# ic-mhm-encoder-buffer-output-only.net
KiCad netlist of a schematic drawn in EAGLE
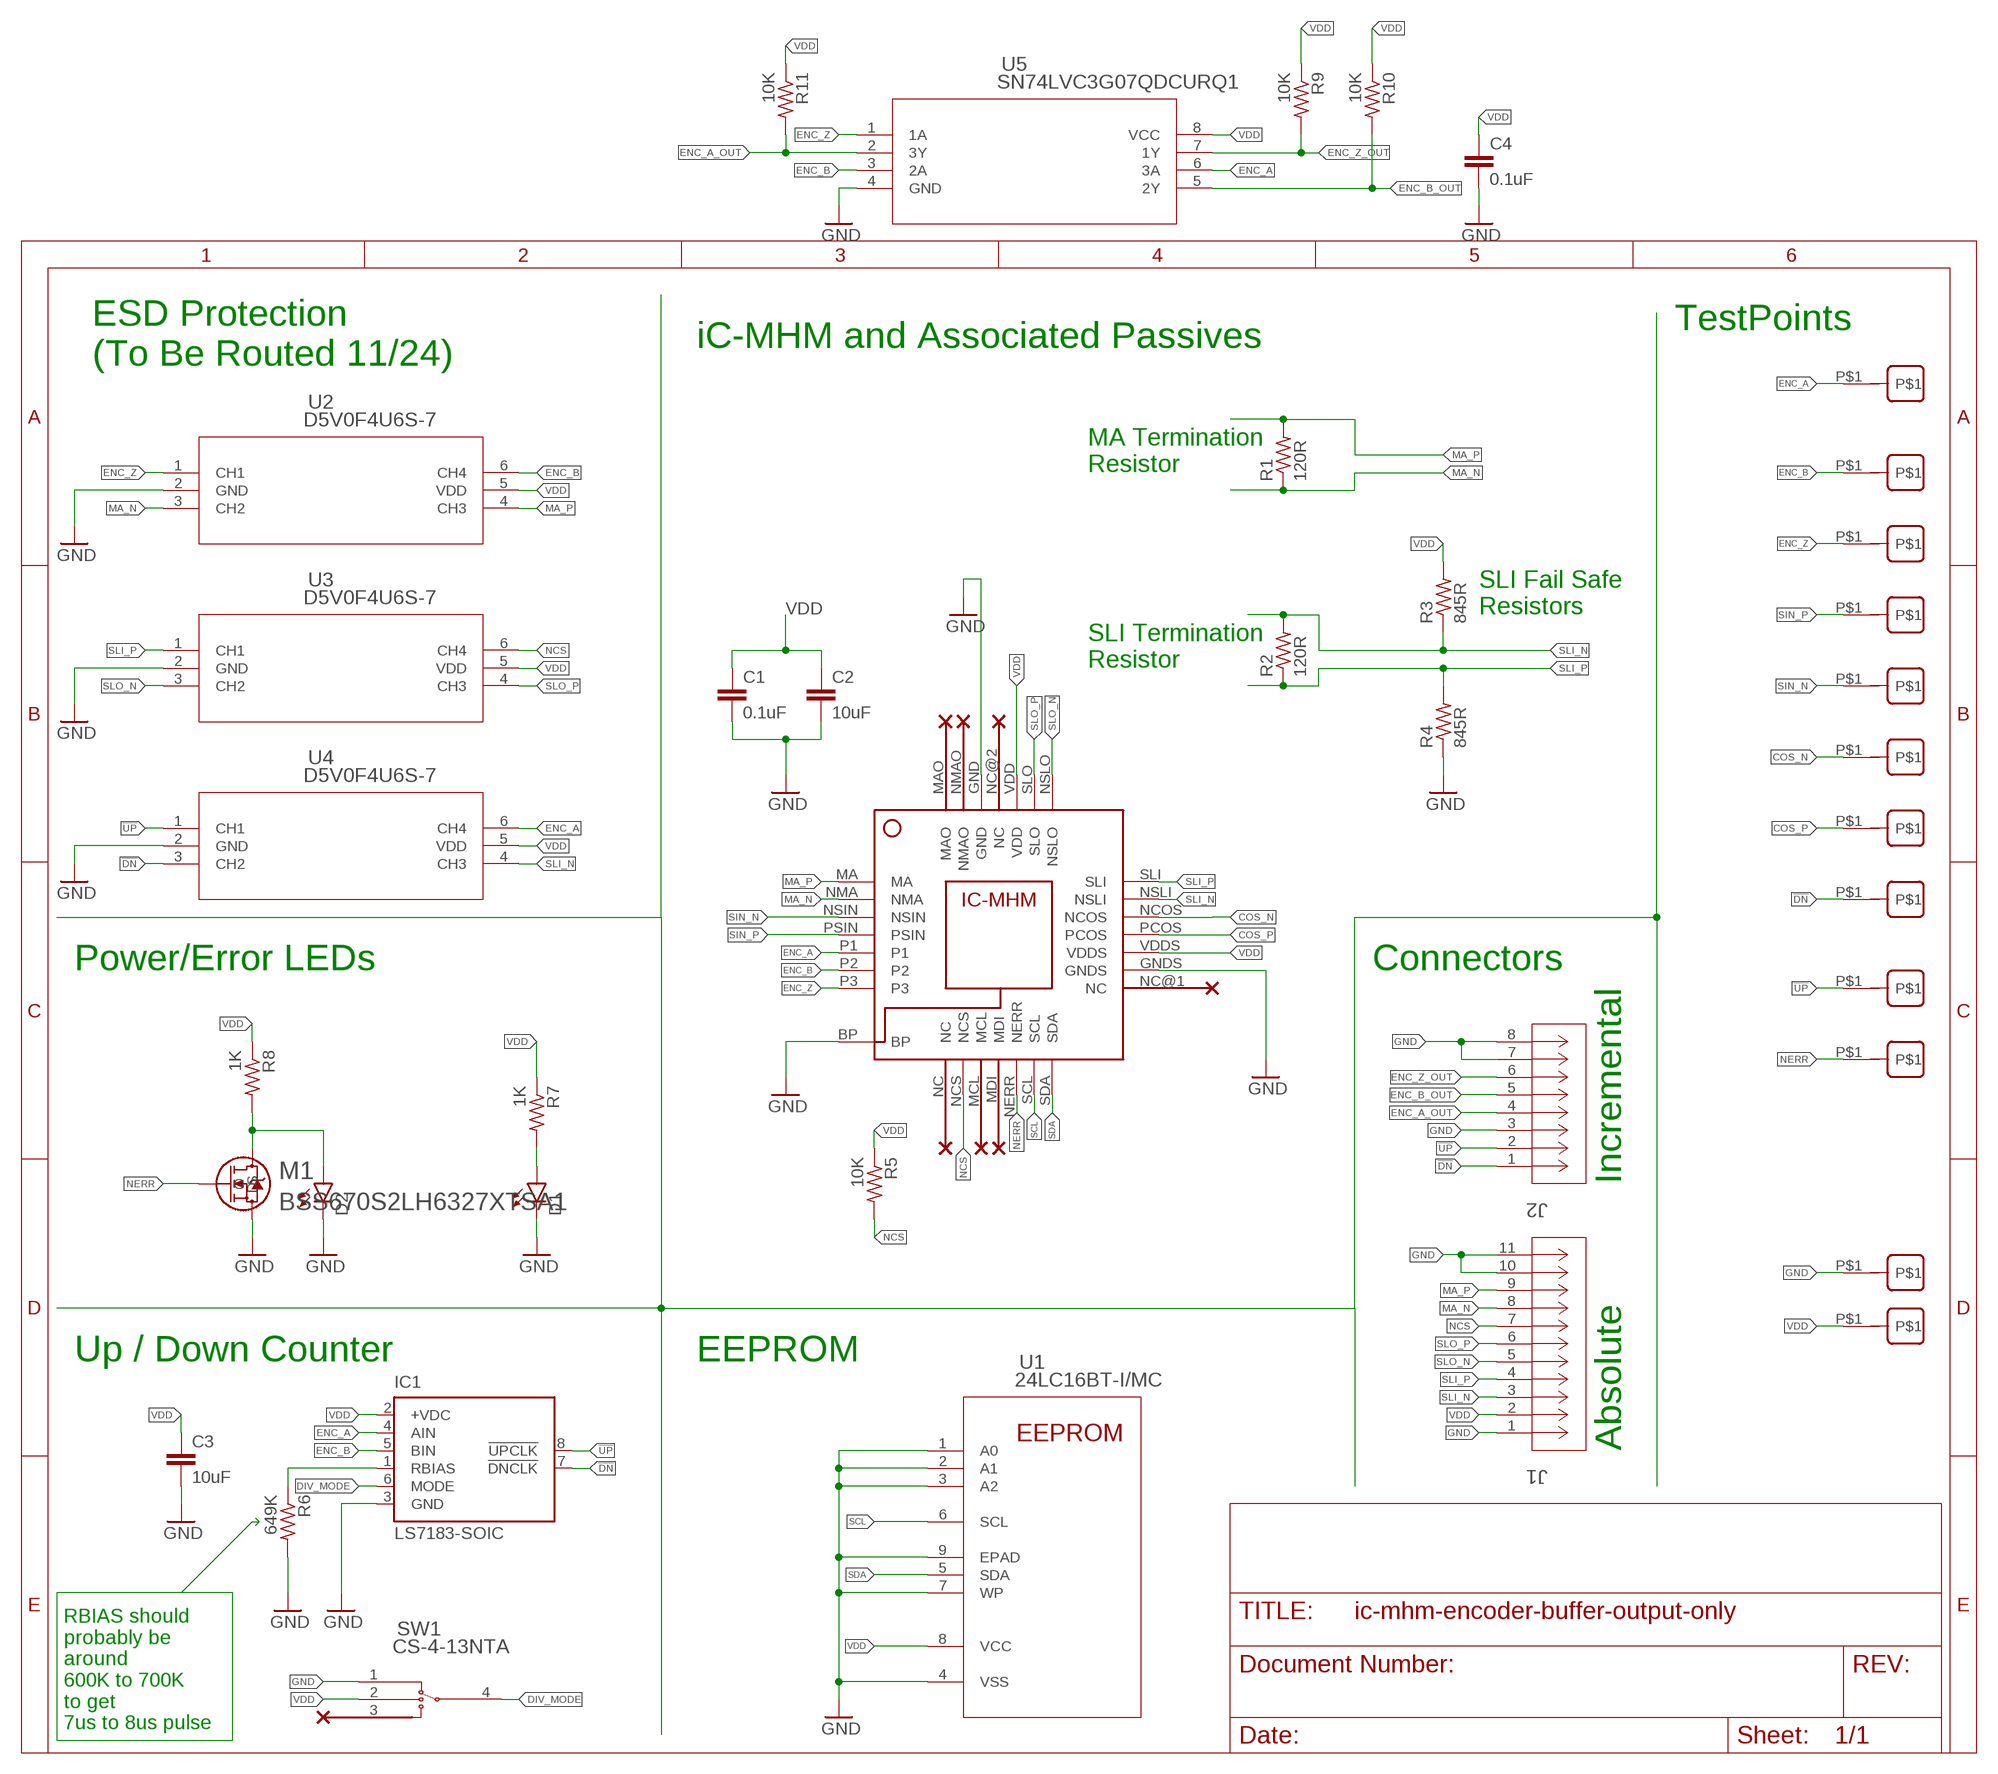
[diagram p0: schematic, sheet 1]

(export (version "E")
  (design (tool "Eeschema 10.0.6"))
  (components
    (comp (ref "C1")
      (value "0.1uF")
      (footprint "eagle-import:C0603")
      (libsource (lib "eagle-import") (part "C-EUC0603"))
    )
    (comp (ref "C2")
      (value "10uF")
      (footprint "eagle-import:C0805")
      (libsource (lib "eagle-import") (part "C-EUC0805"))
    )
    (comp (ref "C3")
      (value "10uF")
      (footprint "eagle-import:C0805")
      (libsource (lib "eagle-import") (part "C-EUC0805"))
    )
    (comp (ref "C4")
      (value "0.1uF")
      (footprint "eagle-import:C0603")
      (libsource (lib "eagle-import") (part "C-EUC0603"))
    )
    (comp (ref "D1")
      (value "LEDSML0603")
      (footprint "eagle-import:SML0603")
      (libsource (lib "eagle-import") (part "LEDSML0603"))
    )
    (comp (ref "D2")
      (value "LEDSML0603")
      (footprint "eagle-import:SML0603")
      (libsource (lib "eagle-import") (part "LEDSML0603"))
    )
    (comp (ref "IC1")
      (value "LS7183-SOIC")
      (footprint "eagle-import:SOIC08")
      (fields
        (field (name "DIGI-KEY_PART_NUMBER") "2808-LS7183N-S-ND")
        (field (name "MF") "LSI")
        (field (name "MP") "LS7183")
      )
      (libsource (lib "eagle-import") (part "LS7183-SOIC"))
    )
    (comp (ref "J1")
      (value "2023960907")
      (footprint "eagle-import:CON_2023960907")
      (fields (field (name "COPYRIGHT") "Copyright (C) 2021 Ultra Librarian. All rights reserved."))
      (libsource (lib "eagle-import") (part "2023960907"))
    )
    (comp (ref "J2")
      (value "2023960607")
      (footprint "eagle-import:CON_2023960607")
      (fields (field (name "COPYRIGHT") "Copyright (C) 2021 Ultra Librarian. All rights reserved."))
      (libsource (lib "eagle-import") (part "2023960607"))
    )
    (comp (ref "M1")
      (value "BSS670S2LH6327XTSA1")
      (footprint "eagle-import:PG-SOT23-3-5_INF")
      (fields (field (name "COPYRIGHT") "Copyright (C) 2021 Ultra Librarian. All rights reserved."))
      (libsource (lib "eagle-import") (part "BSS670S2LH6327XTSA1"))
    )
    (comp (ref "R1")
      (value "120R")
      (footprint "eagle-import:R0603")
      (libsource (lib "eagle-import") (part "R-US_R0603"))
    )
    (comp (ref "R2")
      (value "120R")
      (footprint "eagle-import:R0603")
      (libsource (lib "eagle-import") (part "R-US_R0603"))
    )
    (comp (ref "R3")
      (value "845R")
      (footprint "eagle-import:R0603")
      (libsource (lib "eagle-import") (part "R-US_R0603"))
    )
    (comp (ref "R4")
      (value "845R")
      (footprint "eagle-import:R0603")
      (libsource (lib "eagle-import") (part "R-US_R0603"))
    )
    (comp (ref "R5")
      (value "10K")
      (footprint "eagle-import:R0603")
      (libsource (lib "eagle-import") (part "R-US_R0603"))
    )
    (comp (ref "R6")
      (value "649K")
      (footprint "eagle-import:R0603")
      (libsource (lib "eagle-import") (part "R-US_R0603"))
    )
    (comp (ref "R7")
      (value "1K")
      (footprint "eagle-import:R0603")
      (libsource (lib "eagle-import") (part "R-US_R0603"))
    )
    (comp (ref "R8")
      (value "1K")
      (footprint "eagle-import:R0603")
      (libsource (lib "eagle-import") (part "R-US_R0603"))
    )
    (comp (ref "R9")
      (value "10K")
      (footprint "eagle-import:R0603")
      (libsource (lib "eagle-import") (part "R-US_R0603"))
    )
    (comp (ref "R10")
      (value "10K")
      (footprint "eagle-import:R0603")
      (libsource (lib "eagle-import") (part "R-US_R0603"))
    )
    (comp (ref "R11")
      (value "10K")
      (footprint "eagle-import:R0603")
      (libsource (lib "eagle-import") (part "R-US_R0603"))
    )
    (comp (ref "SW1")
      (value "CS-4-13NTA")
      (footprint "eagle-import:CS-4-13NA_NDC")
      (fields (field (name "COPYRIGHT") "Copyright (C) 2021 Ultra Librarian. All rights reserved."))
      (libsource (lib "eagle-import") (part "CS-4-13NTA"))
    )
    (comp (ref "U$1")
      (value "IC-MHM")
      (footprint "eagle-import:IC-MHM")
      (libsource (lib "eagle-import") (part "IC-MHM"))
    )
    (comp (ref "U$2")
      (value "TESTPOINT_S1751-46")
      (footprint "eagle-import:TESTPOINT_S1751-46")
      (libsource (lib "eagle-import") (part "TESTPOINT_S1751-46"))
    )
    (comp (ref "U$3")
      (value "TESTPOINT_S1751-46")
      (footprint "eagle-import:TESTPOINT_S1751-46")
      (libsource (lib "eagle-import") (part "TESTPOINT_S1751-46"))
    )
    (comp (ref "U$4")
      (value "TESTPOINT_S1751-46")
      (footprint "eagle-import:TESTPOINT_S1751-46")
      (libsource (lib "eagle-import") (part "TESTPOINT_S1751-46"))
    )
    (comp (ref "U$5")
      (value "TESTPOINT_S1751-46")
      (footprint "eagle-import:TESTPOINT_S1751-46")
      (libsource (lib "eagle-import") (part "TESTPOINT_S1751-46"))
    )
    (comp (ref "U$6")
      (value "TESTPOINT_S1751-46")
      (footprint "eagle-import:TESTPOINT_S1751-46")
      (libsource (lib "eagle-import") (part "TESTPOINT_S1751-46"))
    )
    (comp (ref "U$7")
      (value "TESTPOINT_S1751-46")
      (footprint "eagle-import:TESTPOINT_S1751-46")
      (libsource (lib "eagle-import") (part "TESTPOINT_S1751-46"))
    )
    (comp (ref "U$8")
      (value "TESTPOINT_S1751-46")
      (footprint "eagle-import:TESTPOINT_S1751-46")
      (libsource (lib "eagle-import") (part "TESTPOINT_S1751-46"))
    )
    (comp (ref "U$9")
      (value "TESTPOINT_S1751-46")
      (footprint "eagle-import:TESTPOINT_S1751-46")
      (libsource (lib "eagle-import") (part "TESTPOINT_S1751-46"))
    )
    (comp (ref "U$10")
      (value "TESTPOINT_S1751-46")
      (footprint "eagle-import:TESTPOINT_S1751-46")
      (libsource (lib "eagle-import") (part "TESTPOINT_S1751-46"))
    )
    (comp (ref "U$11")
      (value "TESTPOINT_S1751-46")
      (footprint "eagle-import:TESTPOINT_S1751-46")
      (libsource (lib "eagle-import") (part "TESTPOINT_S1751-46"))
    )
    (comp (ref "U$15")
      (value "TESTPOINT_S1751-46")
      (footprint "eagle-import:TESTPOINT_S1751-46")
      (libsource (lib "eagle-import") (part "TESTPOINT_S1751-46"))
    )
    (comp (ref "U$16")
      (value "TESTPOINT_S1751-46")
      (footprint "eagle-import:TESTPOINT_S1751-46")
      (libsource (lib "eagle-import") (part "TESTPOINT_S1751-46"))
    )
    (comp (ref "U1")
      (value "24LC16BT-I/MC")
      (footprint "eagle-import:DFN8_2X3MC_MCH")
      (fields (field (name "COPYRIGHT") "Copyright (C) 2021 Ultra Librarian. All rights reserved."))
      (libsource (lib "eagle-import") (part "24LC16BT-I/MC"))
    )
    (comp (ref "U2")
      (value "D5V0F4U6S-7")
      (footprint "eagle-import:SOT-363_DIO")
      (fields (field (name "COPYRIGHT") "Copyright (C) 2021 Ultra Librarian. All rights reserved."))
      (libsource (lib "eagle-import") (part "D5V0F4U6S-7"))
    )
    (comp (ref "U3")
      (value "D5V0F4U6S-7")
      (footprint "eagle-import:SOT-363_DIO")
      (fields (field (name "COPYRIGHT") "Copyright (C) 2021 Ultra Librarian. All rights reserved."))
      (libsource (lib "eagle-import") (part "D5V0F4U6S-7"))
    )
    (comp (ref "U4")
      (value "D5V0F4U6S-7")
      (footprint "eagle-import:SOT-363_DIO")
      (fields (field (name "COPYRIGHT") "Copyright (C) 2021 Ultra Librarian. All rights reserved."))
      (libsource (lib "eagle-import") (part "D5V0F4U6S-7"))
    )
    (comp (ref "U5")
      (value "SN74LVC3G07QDCURQ1")
      (footprint "eagle-import:DCU8_TEX")
      (fields (field (name "COPYRIGHT") "Copyright (C) 2021 Ultra Librarian. All rights reserved."))
      (libsource (lib "eagle-import") (part "SN74LVC3G07QDCURQ1"))
    )
  )
  (nets
    (net (code "1") (name "/~{DN}") (class "Default")
      (node (ref "IC1") (pin "7") (pinfunction "~{DNCLK}_7") (pintype "input"))
      (node (ref "J2") (pin "1") (pinfunction "1_1") (pintype "passive"))
      (node (ref "U$8") (pin "P$1") (pinfunction "P$1_P$1") (pintype "bidirectional"))
      (node (ref "U4") (pin "3") (pinfunction "CH2_3") (pintype "passive"))
    )
    (net (code "2") (name "/~{UP}") (class "Default")
      (node (ref "IC1") (pin "8") (pinfunction "~{UPCLK}_8") (pintype "input"))
      (node (ref "J2") (pin "2") (pinfunction "2_2") (pintype "passive"))
      (node (ref "U$9") (pin "P$1") (pinfunction "P$1_P$1") (pintype "bidirectional"))
      (node (ref "U4") (pin "1") (pinfunction "CH1_1") (pintype "passive"))
    )
    (net (code "3") (name "COS_N") (class "Default")
      (node (ref "U$1") (pin "NCOS") (pinfunction "NCOS_NCOS") (pintype "bidirectional"))
      (node (ref "U$7") (pin "P$1") (pinfunction "P$1_P$1") (pintype "bidirectional"))
    )
    (net (code "4") (name "COS_P") (class "Default")
      (node (ref "U$1") (pin "PCOS") (pinfunction "PCOS_PCOS") (pintype "bidirectional"))
      (node (ref "U$11") (pin "P$1") (pinfunction "P$1_P$1") (pintype "bidirectional"))
    )
    (net (code "5") (name "DIV_MODE") (class "Default")
      (node (ref "IC1") (pin "6") (pinfunction "MODE_6") (pintype "input"))
      (node (ref "SW1") (pin "4") (pinfunction "4_4") (pintype "passive"))
    )
    (net (code "6") (name "ENC_A") (class "Default")
      (node (ref "IC1") (pin "4") (pinfunction "AIN_4") (pintype "input"))
      (node (ref "U$1") (pin "P1") (pinfunction "P1_P1") (pintype "bidirectional"))
      (node (ref "U$2") (pin "P$1") (pinfunction "P$1_P$1") (pintype "bidirectional"))
      (node (ref "U4") (pin "6") (pinfunction "CH4_6") (pintype "passive"))
      (node (ref "U5") (pin "6") (pinfunction "3A_6") (pintype "input"))
    )
    (net (code "7") (name "ENC_A_OUT") (class "Default")
      (node (ref "J2") (pin "4") (pinfunction "4_4") (pintype "passive"))
      (node (ref "R11") (pin "2") (pinfunction "2_2") (pintype "passive"))
      (node (ref "U5") (pin "2") (pinfunction "3Y_2") (pintype "output"))
    )
    (net (code "8") (name "ENC_B") (class "Default")
      (node (ref "IC1") (pin "5") (pinfunction "BIN_5") (pintype "input"))
      (node (ref "U$1") (pin "P2") (pinfunction "P2_P2") (pintype "bidirectional"))
      (node (ref "U$3") (pin "P$1") (pinfunction "P$1_P$1") (pintype "bidirectional"))
      (node (ref "U2") (pin "6") (pinfunction "CH4_6") (pintype "passive"))
      (node (ref "U5") (pin "3") (pinfunction "2A_3") (pintype "input"))
    )
    (net (code "9") (name "ENC_B_OUT") (class "Default")
      (node (ref "J2") (pin "5") (pinfunction "5_5") (pintype "passive"))
      (node (ref "R10") (pin "2") (pinfunction "2_2") (pintype "passive"))
      (node (ref "U5") (pin "5") (pinfunction "2Y_5") (pintype "output"))
    )
    (net (code "10") (name "ENC_Z") (class "Default")
      (node (ref "U$1") (pin "P3") (pinfunction "P3_P3") (pintype "bidirectional"))
      (node (ref "U$4") (pin "P$1") (pinfunction "P$1_P$1") (pintype "bidirectional"))
      (node (ref "U2") (pin "1") (pinfunction "CH1_1") (pintype "passive"))
      (node (ref "U5") (pin "1") (pinfunction "1A_1") (pintype "input"))
    )
    (net (code "11") (name "ENC_Z_OUT") (class "Default")
      (node (ref "J2") (pin "6") (pinfunction "6_6") (pintype "passive"))
      (node (ref "R9") (pin "2") (pinfunction "2_2") (pintype "passive"))
      (node (ref "U5") (pin "7") (pinfunction "1Y_7") (pintype "output"))
    )
    (net (code "12") (name "GND") (class "Default")
      (node (ref "C1") (pin "2") (pinfunction "2_2") (pintype "passive"))
      (node (ref "C2") (pin "2") (pinfunction "2_2") (pintype "passive"))
      (node (ref "C3") (pin "2") (pinfunction "2_2") (pintype "passive"))
      (node (ref "C4") (pin "2") (pinfunction "2_2") (pintype "passive"))
      (node (ref "D1") (pin "C") (pinfunction "C_C") (pintype "passive"))
      (node (ref "D2") (pin "C") (pinfunction "C_C") (pintype "passive"))
      (node (ref "IC1") (pin "3") (pinfunction "GND_3") (pintype "power_in"))
      (node (ref "J1") (pin "1") (pinfunction "1_1") (pintype "passive"))
      (node (ref "J1") (pin "10") (pinfunction "10_10") (pintype "passive"))
      (node (ref "J1") (pin "11") (pinfunction "11_11") (pintype "passive"))
      (node (ref "J2") (pin "3") (pinfunction "3_3") (pintype "passive"))
      (node (ref "J2") (pin "7") (pinfunction "7_7") (pintype "passive"))
      (node (ref "J2") (pin "8") (pinfunction "8_8") (pintype "passive"))
      (node (ref "M1") (pin "2") (pinfunction "S_2") (pintype "passive"))
      (node (ref "R4") (pin "1") (pinfunction "1_1") (pintype "passive"))
      (node (ref "R6") (pin "2") (pinfunction "2_2") (pintype "passive"))
      (node (ref "SW1") (pin "1") (pinfunction "1_1") (pintype "passive"))
      (node (ref "U$1") (pin "BP") (pinfunction "BP_BP") (pintype "bidirectional"))
      (node (ref "U$1") (pin "GND") (pinfunction "GND_GND") (pintype "bidirectional"))
      (node (ref "U$1") (pin "GNDS") (pinfunction "GNDS_GNDS") (pintype "bidirectional"))
      (node (ref "U$15") (pin "P$1") (pinfunction "P$1_P$1") (pintype "bidirectional"))
      (node (ref "U1") (pin "1") (pinfunction "A0_1") (pintype "input"))
      (node (ref "U1") (pin "2") (pinfunction "A1_2") (pintype "input"))
      (node (ref "U1") (pin "3") (pinfunction "A2_3") (pintype "input"))
      (node (ref "U1") (pin "4") (pinfunction "VSS_4") (pintype "power_in"))
      (node (ref "U1") (pin "7") (pinfunction "WP_7") (pintype "passive"))
      (node (ref "U1") (pin "9") (pinfunction "EPAD_9") (pintype "passive"))
      (node (ref "U2") (pin "2") (pinfunction "GND_2") (pintype "power_in"))
      (node (ref "U3") (pin "2") (pinfunction "GND_2") (pintype "power_in"))
      (node (ref "U4") (pin "2") (pinfunction "GND_2") (pintype "power_in"))
      (node (ref "U5") (pin "4") (pinfunction "GND_4") (pintype "power_in"))
    )
    (net (code "13") (name "MA_N") (class "Default")
      (node (ref "J1") (pin "8") (pinfunction "8_8") (pintype "passive"))
      (node (ref "R1") (pin "1") (pinfunction "1_1") (pintype "passive"))
      (node (ref "U$1") (pin "NMA") (pinfunction "NMA_NMA") (pintype "bidirectional"))
      (node (ref "U2") (pin "3") (pinfunction "CH2_3") (pintype "passive"))
    )
    (net (code "14") (name "MA_P") (class "Default")
      (node (ref "J1") (pin "9") (pinfunction "9_9") (pintype "passive"))
      (node (ref "R1") (pin "2") (pinfunction "2_2") (pintype "passive"))
      (node (ref "U$1") (pin "MA") (pinfunction "MA_MA") (pintype "bidirectional"))
      (node (ref "U2") (pin "4") (pinfunction "CH3_4") (pintype "passive"))
    )
    (net (code "15") (name "NCS") (class "Default")
      (node (ref "J1") (pin "7") (pinfunction "7_7") (pintype "passive"))
      (node (ref "R5") (pin "2") (pinfunction "2_2") (pintype "passive"))
      (node (ref "U$1") (pin "NCS") (pinfunction "NCS_NCS") (pintype "bidirectional"))
      (node (ref "U3") (pin "6") (pinfunction "CH4_6") (pintype "passive"))
    )
    (net (code "16") (name "NERR") (class "Default")
      (node (ref "M1") (pin "1") (pinfunction "G_1") (pintype "passive"))
      (node (ref "U$1") (pin "NERR") (pinfunction "NERR_NERR") (pintype "bidirectional"))
      (node (ref "U$10") (pin "P$1") (pinfunction "P$1_P$1") (pintype "bidirectional"))
    )
    (net (code "17") (name "Net-(D1-PadA)") (class "Default")
      (node (ref "D1") (pin "A") (pinfunction "A_A") (pintype "passive"))
      (node (ref "R7") (pin "2") (pinfunction "2_2") (pintype "passive"))
    )
    (net (code "18") (name "Net-(IC1-RBIAS)") (class "Default")
      (node (ref "IC1") (pin "1") (pinfunction "RBIAS_1") (pintype "input"))
      (node (ref "R6") (pin "1") (pinfunction "1_1") (pintype "passive"))
    )
    (net (code "19") (name "Net-(M1-D)") (class "Default")
      (node (ref "D2") (pin "A") (pinfunction "A_A") (pintype "passive"))
      (node (ref "M1") (pin "3") (pinfunction "D_3") (pintype "passive"))
      (node (ref "R8") (pin "2") (pinfunction "2_2") (pintype "passive"))
    )
    (net (code "20") (name "SCL") (class "Default")
      (node (ref "U$1") (pin "SCL") (pinfunction "SCL_SCL") (pintype "bidirectional"))
      (node (ref "U1") (pin "6") (pinfunction "SCL_6") (pintype "input"))
    )
    (net (code "21") (name "SDA") (class "Default")
      (node (ref "U$1") (pin "SDA") (pinfunction "SDA_SDA") (pintype "bidirectional"))
      (node (ref "U1") (pin "5") (pinfunction "SDA_5") (pintype "bidirectional"))
    )
    (net (code "22") (name "SIN_N") (class "Default")
      (node (ref "U$1") (pin "NSIN") (pinfunction "NSIN_NSIN") (pintype "bidirectional"))
      (node (ref "U$6") (pin "P$1") (pinfunction "P$1_P$1") (pintype "bidirectional"))
    )
    (net (code "23") (name "SIN_P") (class "Default")
      (node (ref "U$1") (pin "PSIN") (pinfunction "PSIN_PSIN") (pintype "bidirectional"))
      (node (ref "U$5") (pin "P$1") (pinfunction "P$1_P$1") (pintype "bidirectional"))
    )
    (net (code "24") (name "SLI_N") (class "Default")
      (node (ref "J1") (pin "3") (pinfunction "3_3") (pintype "passive"))
      (node (ref "R2") (pin "2") (pinfunction "2_2") (pintype "passive"))
      (node (ref "R3") (pin "1") (pinfunction "1_1") (pintype "passive"))
      (node (ref "U$1") (pin "NSLI") (pinfunction "NSLI_NSLI") (pintype "bidirectional"))
      (node (ref "U4") (pin "4") (pinfunction "CH3_4") (pintype "passive"))
    )
    (net (code "25") (name "SLI_P") (class "Default")
      (node (ref "J1") (pin "4") (pinfunction "4_4") (pintype "passive"))
      (node (ref "R2") (pin "1") (pinfunction "1_1") (pintype "passive"))
      (node (ref "R4") (pin "2") (pinfunction "2_2") (pintype "passive"))
      (node (ref "U$1") (pin "SLI") (pinfunction "SLI_SLI") (pintype "bidirectional"))
      (node (ref "U3") (pin "1") (pinfunction "CH1_1") (pintype "passive"))
    )
    (net (code "26") (name "SLO_N") (class "Default")
      (node (ref "J1") (pin "5") (pinfunction "5_5") (pintype "passive"))
      (node (ref "U$1") (pin "NSLO") (pinfunction "NSLO_NSLO") (pintype "bidirectional"))
      (node (ref "U3") (pin "3") (pinfunction "CH2_3") (pintype "passive"))
    )
    (net (code "27") (name "SLO_P") (class "Default")
      (node (ref "J1") (pin "6") (pinfunction "6_6") (pintype "passive"))
      (node (ref "U$1") (pin "SLO") (pinfunction "SLO_SLO") (pintype "bidirectional"))
      (node (ref "U3") (pin "4") (pinfunction "CH3_4") (pintype "passive"))
    )
    (net (code "28") (name "VDD") (class "Default")
      (node (ref "C1") (pin "1") (pinfunction "1_1") (pintype "passive"))
      (node (ref "C2") (pin "1") (pinfunction "1_1") (pintype "passive"))
      (node (ref "C3") (pin "1") (pinfunction "1_1") (pintype "passive"))
      (node (ref "C4") (pin "1") (pinfunction "1_1") (pintype "passive"))
      (node (ref "IC1") (pin "2") (pinfunction "+VDC_2") (pintype "input"))
      (node (ref "J1") (pin "2") (pinfunction "2_2") (pintype "passive"))
      (node (ref "R10") (pin "1") (pinfunction "1_1") (pintype "passive"))
      (node (ref "R11") (pin "1") (pinfunction "1_1") (pintype "passive"))
      (node (ref "R3") (pin "2") (pinfunction "2_2") (pintype "passive"))
      (node (ref "R5") (pin "1") (pinfunction "1_1") (pintype "passive"))
      (node (ref "R7") (pin "1") (pinfunction "1_1") (pintype "passive"))
      (node (ref "R8") (pin "1") (pinfunction "1_1") (pintype "passive"))
      (node (ref "R9") (pin "1") (pinfunction "1_1") (pintype "passive"))
      (node (ref "SW1") (pin "2") (pinfunction "2_2") (pintype "passive"))
      (node (ref "U$1") (pin "VDD") (pinfunction "VDD_VDD") (pintype "bidirectional"))
      (node (ref "U$1") (pin "VDDS") (pinfunction "VDDS_VDDS") (pintype "bidirectional"))
      (node (ref "U$16") (pin "P$1") (pinfunction "P$1_P$1") (pintype "bidirectional"))
      (node (ref "U1") (pin "8") (pinfunction "VCC_8") (pintype "power_in"))
      (node (ref "U2") (pin "5") (pinfunction "VDD_5") (pintype "power_in"))
      (node (ref "U3") (pin "5") (pinfunction "VDD_5") (pintype "power_in"))
      (node (ref "U4") (pin "5") (pinfunction "VDD_5") (pintype "power_in"))
      (node (ref "U5") (pin "8") (pinfunction "VCC_8") (pintype "power_in"))
    )
    (net (code "29") (name "unconnected-(SW1-Pad3)") (class "Default")
      (node (ref "SW1") (pin "3") (pinfunction "3_3") (pintype "passive"))
    )
    (net (code "30") (name "unconnected-(U$1-NC-PadNC@1)") (class "Default")
      (node (ref "U$1") (pin "NC@1") (pinfunction "NC_NC@1") (pintype "bidirectional"))
    )
    (net (code "31") (name "unconnected-(U$1-NC-PadNC@2)") (class "Default")
      (node (ref "U$1") (pin "NC@2") (pinfunction "NC_NC@2") (pintype "bidirectional"))
    )
    (net (code "32") (name "unconnected-(U$1-PadMAO)") (class "Default")
      (node (ref "U$1") (pin "MAO") (pinfunction "MAO_MAO") (pintype "bidirectional"))
    )
    (net (code "33") (name "unconnected-(U$1-PadMCL)") (class "Default")
      (node (ref "U$1") (pin "MCL") (pinfunction "MCL_MCL") (pintype "bidirectional"))
    )
    (net (code "34") (name "unconnected-(U$1-PadMDI)") (class "Default")
      (node (ref "U$1") (pin "MDI") (pinfunction "MDI_MDI") (pintype "bidirectional"))
    )
    (net (code "35") (name "unconnected-(U$1-PadNC)") (class "Default")
      (node (ref "U$1") (pin "NC") (pinfunction "NC_NC") (pintype "bidirectional"))
    )
    (net (code "36") (name "unconnected-(U$1-PadNMAO)") (class "Default")
      (node (ref "U$1") (pin "NMAO") (pinfunction "NMAO_NMAO") (pintype "bidirectional"))
    )
  )
)
